# Ethernet.net
KiCad netlist of a schematic drawn in Altium Designer
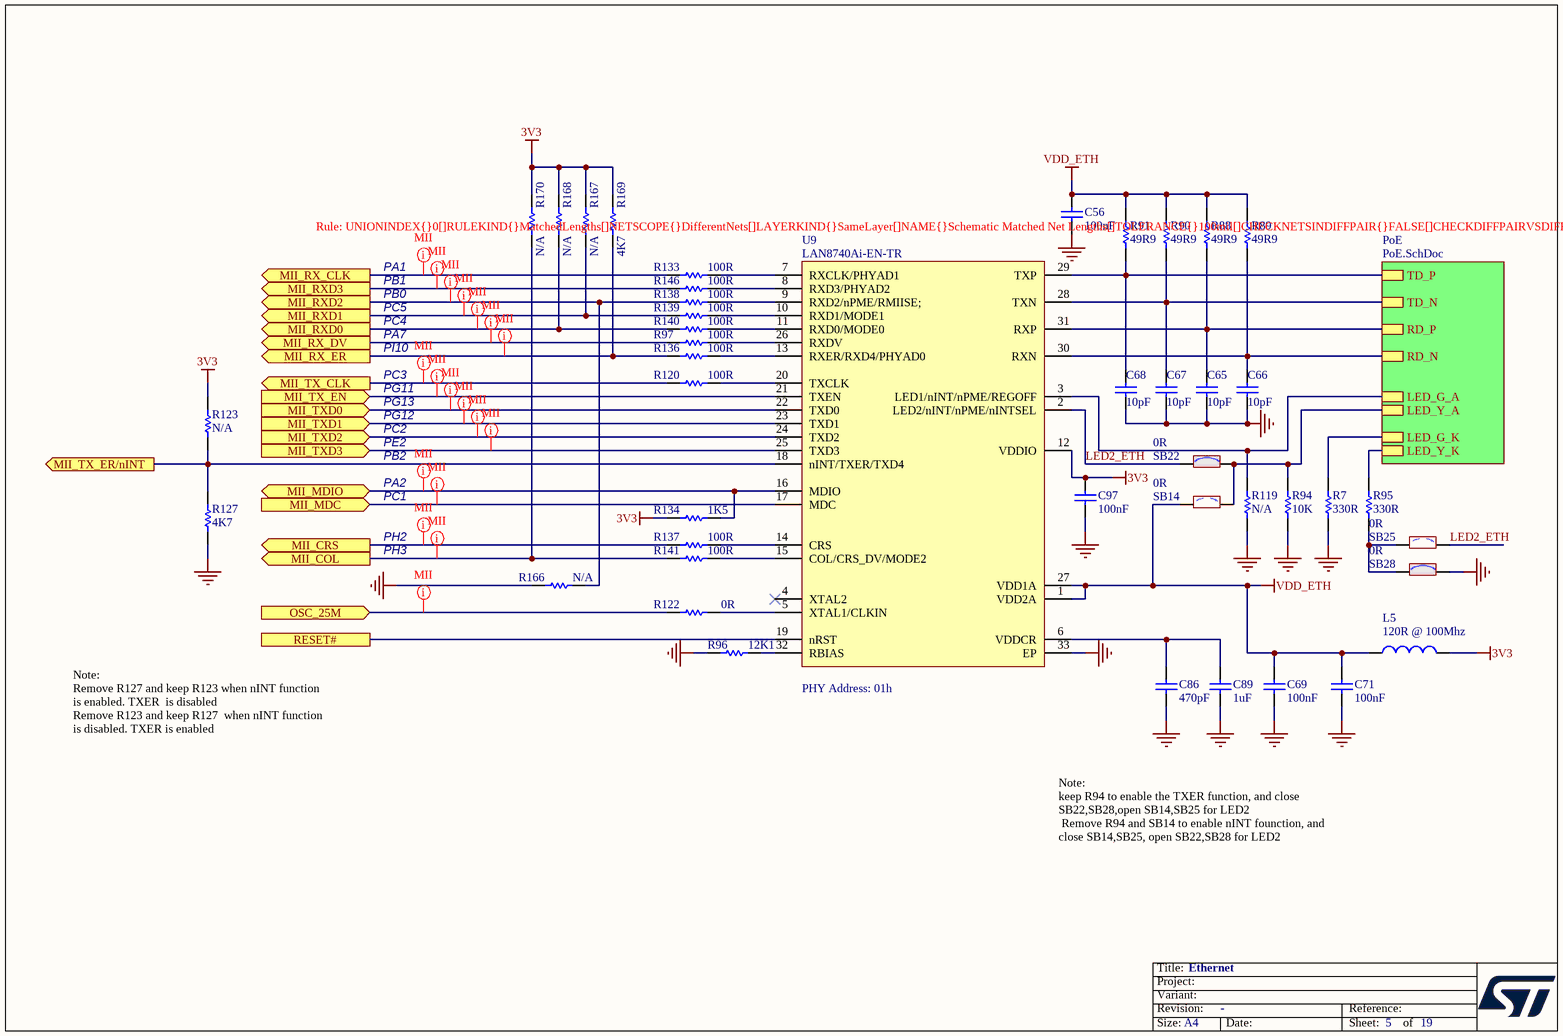
[diagram p0: Ethernet.SchDoc]

(export (version "E")
  (design (tool "Eeschema 10.0.6"))
  (components
    (comp (ref "C56")
      (value "100nF")
      (footprint "C0402")
      (description "Capacitor, MLCC, 100nF, 16V, X7R, +/-10%, 0402, T=0.5mm")
      (fields
        (field (name "INTERNAL_PART_NUMBER") "MCD-00006")
        (field (name "MANUFACTURER_PART_NUMBER") "CC0402KRX7R7BB104")
      )
      (libsource (lib "MCD_PARTS_database") (part "Capacitor"))
    )
    (comp (ref "C65")
      (value "10pF")
      (footprint "C0603")
      (description "Capacitor, MLCC, 10pF, 50V, NPO, 5%, 0603, T=0,8mm")
      (fields
        (field (name "INTERNAL_PART_NUMBER") "MCD-00637")
        (field (name "MANUFACTURER_PART_NUMBER") "CC0603JRNPO9BN100")
        (field (name "PROVIDED_BY") "subcon")
      )
      (libsource (lib "MCD_PARTS_database") (part "Capacitor"))
    )
    (comp (ref "C66")
      (value "10pF")
      (footprint "C0603")
      (description "Capacitor, MLCC, 10pF, 50V, NPO, 5%, 0603, T=0,8mm")
      (fields
        (field (name "INTERNAL_PART_NUMBER") "MCD-00637")
        (field (name "MANUFACTURER_PART_NUMBER") "CC0603JRNPO9BN100")
        (field (name "PROVIDED_BY") "subcon")
      )
      (libsource (lib "MCD_PARTS_database") (part "Capacitor"))
    )
    (comp (ref "C67")
      (value "10pF")
      (footprint "C0603")
      (description "Capacitor, MLCC, 10pF, 50V, NPO, 5%, 0603, T=0,8mm")
      (fields
        (field (name "INTERNAL_PART_NUMBER") "MCD-00637")
        (field (name "MANUFACTURER_PART_NUMBER") "CC0603JRNPO9BN100")
        (field (name "PROVIDED_BY") "subcon")
      )
      (libsource (lib "MCD_PARTS_database") (part "Capacitor"))
    )
    (comp (ref "C68")
      (value "10pF")
      (footprint "C0603")
      (description "Capacitor, MLCC, 10pF, 50V, NPO, 5%, 0603, T=0,8mm")
      (fields
        (field (name "INTERNAL_PART_NUMBER") "MCD-00637")
        (field (name "MANUFACTURER_PART_NUMBER") "CC0603JRNPO9BN100")
        (field (name "PROVIDED_BY") "subcon")
      )
      (libsource (lib "MCD_PARTS_database") (part "Capacitor"))
    )
    (comp (ref "C69")
      (value "100nF")
      (footprint "C0402")
      (description "Capacitor, MLCC, 100nF, 16V, X7R, +/-10%, 0402, T=0.5mm")
      (fields
        (field (name "INTERNAL_PART_NUMBER") "MCD-00006")
        (field (name "MANUFACTURER_PART_NUMBER") "CC0402KRX7R7BB104")
      )
      (libsource (lib "MCD_PARTS_database") (part "Capacitor"))
    )
    (comp (ref "C71")
      (value "100nF")
      (footprint "C0402")
      (description "Capacitor, MLCC, 100nF, 16V, X7R, +/-10%, 0402, T=0.5mm")
      (fields
        (field (name "INTERNAL_PART_NUMBER") "MCD-00006")
        (field (name "MANUFACTURER_PART_NUMBER") "CC0402KRX7R7BB104")
      )
      (libsource (lib "MCD_PARTS_database") (part "Capacitor"))
    )
    (comp (ref "C86")
      (value "470pF")
      (footprint "C0402")
      (description "Capacitor, MLCC, 470pF, 50V, NPO, 5%, 0402, T=0,5mm")
      (fields
        (field (name "INTERNAL_PART_NUMBER") "MCD-00724")
        (field (name "MANUFACTURER_PART_NUMBER") "CC0402JRNPO9BN471")
        (field (name "PROVIDED_BY") "Subcon")
      )
      (libsource (lib "MCD_PARTS_database") (part "Capacitor"))
    )
    (comp (ref "C89")
      (value "1uF")
      (footprint "C0603")
      (description "Capacitor, MLCC, 1uF, 16V, X5R, 10%, 0603, T=0,8mm")
      (fields
        (field (name "INTERNAL_PART_NUMBER") "MCD-00010")
        (field (name "MANUFACTURER_PART_NUMBER") "CC0603KRX5R7BB105")
        (field (name "PROVIDED_BY") "Subcon")
      )
      (libsource (lib "MCD_PARTS_database") (part "Capacitor"))
    )
    (comp (ref "C97")
      (value "100nF")
      (footprint "C0402")
      (description "Capacitor, MLCC, 100nF, 16V, X7R, +/-10%, 0402, T=0.5mm")
      (fields
        (field (name "INTERNAL_PART_NUMBER") "MCD-00006")
        (field (name "MANUFACTURER_PART_NUMBER") "CC0402KRX7R7BB104")
      )
      (libsource (lib "MCD_PARTS_database") (part "Capacitor"))
    )
    (comp (ref "L5")
      (value "120R @ 100Mhz")
      (footprint "FIL_0603_H0P65")
      (description "Bead,120R at 100Mhz,2A,0603")
      (fields
        (field (name "INTERNAL_PART_NUMBER") "MCD-00306")
        (field (name "MANUFACTURER_PART_NUMBER") "BLM18PG121SN1D")
        (field (name "PROVIDED_BY") "Subcon")
      )
      (libsource (lib "MCD_PARTS_database") (part "BEAD"))
    )
    (comp (ref "R7")
      (value "330R")
      (footprint "R0402")
      (description "Resistor,330R,0402,1%,1/16W")
      (fields
        (field (name "INTERNAL_PART_NUMBER") "MCD-00062")
        (field (name "MANUFACTURER_PART_NUMBER") "RC0402FR-07330RL")
        (field (name "PROVIDED_BY") "Subcon")
      )
      (libsource (lib "MCD_PARTS_database") (part "Resistor"))
    )
    (comp (ref "R88")
      (value "49R9")
      (footprint "R0402")
      (description "Resistor,49R9,0402,1%,1/16W")
      (fields
        (field (name "INTERNAL_PART_NUMBER") "MCD-00565")
        (field (name "MANUFACTURER_PART_NUMBER") "RC0402FR-0749R9L")
        (field (name "PROVIDED_BY") "Subcon")
      )
      (libsource (lib "MCD_PARTS_database") (part "Resistor"))
    )
    (comp (ref "R89")
      (value "49R9")
      (footprint "R0402")
      (description "Resistor,49R9,0402,1%,1/16W")
      (fields
        (field (name "INTERNAL_PART_NUMBER") "MCD-00565")
        (field (name "MANUFACTURER_PART_NUMBER") "RC0402FR-0749R9L")
        (field (name "PROVIDED_BY") "Subcon")
      )
      (libsource (lib "MCD_PARTS_database") (part "Resistor"))
    )
    (comp (ref "R90")
      (value "49R9")
      (footprint "R0402")
      (description "Resistor,49R9,0402,1%,1/16W")
      (fields
        (field (name "INTERNAL_PART_NUMBER") "MCD-00565")
        (field (name "MANUFACTURER_PART_NUMBER") "RC0402FR-0749R9L")
        (field (name "PROVIDED_BY") "Subcon")
      )
      (libsource (lib "MCD_PARTS_database") (part "Resistor"))
    )
    (comp (ref "R91")
      (value "49R9")
      (footprint "R0402")
      (description "Resistor,49R9,0402,1%,1/16W")
      (fields
        (field (name "INTERNAL_PART_NUMBER") "MCD-00565")
        (field (name "MANUFACTURER_PART_NUMBER") "RC0402FR-0749R9L")
        (field (name "PROVIDED_BY") "Subcon")
      )
      (libsource (lib "MCD_PARTS_database") (part "Resistor"))
    )
    (comp (ref "R94")
      (value "10K")
      (footprint "R0402")
      (description "Resistor,10K,0402,1%,1/16W")
      (fields
        (field (name "INTERNAL_PART_NUMBER") "MCD-00053")
        (field (name "MANUFACTURER_PART_NUMBER") "RC0402FR-0710KL")
        (field (name "PROVIDED_BY") "subcon")
      )
      (libsource (lib "MCD_PARTS_database") (part "Resistor"))
    )
    (comp (ref "R95")
      (value "330R")
      (footprint "R0402")
      (description "Resistor,330R,0402,1%,1/16W")
      (fields
        (field (name "INTERNAL_PART_NUMBER") "MCD-00062")
        (field (name "MANUFACTURER_PART_NUMBER") "RC0402FR-07330RL")
        (field (name "PROVIDED_BY") "Subcon")
      )
      (libsource (lib "MCD_PARTS_database") (part "Resistor"))
    )
    (comp (ref "R96")
      (value "12K1")
      (footprint "R0402")
      (description "Resistor,12K1,0402,1%,1/16W")
      (fields
        (field (name "INTERNAL_PART_NUMBER") "MCD-00723")
        (field (name "MANUFACTURER_PART_NUMBER") "RC0402FR-0712K1L")
        (field (name "PROVIDED_BY") "Subcon")
      )
      (libsource (lib "MCD_PARTS_database") (part "Resistor"))
    )
    (comp (ref "R97")
      (value "100R")
      (footprint "R0402")
      (description "Resistor, 100R, 0402, +/- 1%, 1/16W")
      (fields
        (field (name "INTERNAL_PART_NUMBER") "MCD-00067")
        (field (name "MANUFACTURER_PART_NUMBER") "RC0402FR-07100RL")
      )
      (libsource (lib "MCD_PARTS_database") (part "Resistor"))
    )
    (comp (ref "R119")
      (value "N/A")
      (footprint "R0402")
      (description "Resistor,10K,0402,1%,1/16W")
      (fields
        (field (name "INTERNAL_PART_NUMBER") "MCD-00053")
        (field (name "MANUFACTURER_PART_NUMBER") "RC0402FR-0710KL")
        (field (name "PROVIDED_BY") "subcon")
      )
      (libsource (lib "MCD_PARTS_database") (part "Resistor"))
    )
    (comp (ref "R120")
      (value "100R")
      (footprint "R0402")
      (description "Resistor, 100R, 0402, +/- 1%, 1/16W")
      (fields
        (field (name "INTERNAL_PART_NUMBER") "MCD-00067")
        (field (name "MANUFACTURER_PART_NUMBER") "RC0402FR-07100RL")
      )
      (libsource (lib "MCD_PARTS_database") (part "Resistor"))
    )
    (comp (ref "R122")
      (value "0R")
      (footprint "R0402")
      (description "Resistor,0R,0402,5%,1/16W")
      (fields
        (field (name "INTERNAL_PART_NUMBER") "MCD-00052")
        (field (name "MANUFACTURER_PART_NUMBER") "RC0402JR-070RL")
        (field (name "PROVIDED_BY") "Subcon")
      )
      (libsource (lib "MCD_PARTS_database") (part "Resistor"))
    )
    (comp (ref "R123")
      (value "N/A")
      (footprint "R0402")
      (description "Resistor,4K7,0402,1%,1/16W")
      (fields
        (field (name "INTERNAL_PART_NUMBER") "MCD-00065")
        (field (name "MANUFACTURER_PART_NUMBER") "RC0402FR-074K7L")
        (field (name "PROVIDED_BY") "Subcon")
      )
      (libsource (lib "MCD_PARTS_database") (part "Resistor"))
    )
    (comp (ref "R127")
      (value "4K7")
      (footprint "R0402")
      (description "Resistor,4K7,0402,1%,1/16W")
      (fields
        (field (name "INTERNAL_PART_NUMBER") "MCD-00065")
        (field (name "MANUFACTURER_PART_NUMBER") "RC0402FR-074K7L")
        (field (name "PROVIDED_BY") "Subcon")
      )
      (libsource (lib "MCD_PARTS_database") (part "Resistor"))
    )
    (comp (ref "R133")
      (value "100R")
      (footprint "R0402")
      (description "Resistor, 100R, 0402, +/- 1%, 1/16W")
      (fields
        (field (name "INTERNAL_PART_NUMBER") "MCD-00067")
        (field (name "MANUFACTURER_PART_NUMBER") "RC0402FR-07100RL")
      )
      (libsource (lib "MCD_PARTS_database") (part "Resistor"))
    )
    (comp (ref "R134")
      (value "1K5")
      (footprint "R0603")
      (description "Resistor,1K5,0603,1%,1/10W")
      (fields
        (field (name "INTERNAL_PART_NUMBER") "MCD-00217")
        (field (name "MANUFACTURER_PART_NUMBER") "RC0603FR-071K5L")
        (field (name "PROVIDED_BY") "Subcon")
      )
      (libsource (lib "MCD_PARTS_database") (part "Resistor"))
    )
    (comp (ref "R136")
      (value "100R")
      (footprint "R0402")
      (description "Resistor, 100R, 0402, +/- 1%, 1/16W")
      (fields
        (field (name "INTERNAL_PART_NUMBER") "MCD-00067")
        (field (name "MANUFACTURER_PART_NUMBER") "RC0402FR-07100RL")
      )
      (libsource (lib "MCD_PARTS_database") (part "Resistor"))
    )
    (comp (ref "R137")
      (value "100R")
      (footprint "R0402")
      (description "Resistor, 100R, 0402, +/- 1%, 1/16W")
      (fields
        (field (name "INTERNAL_PART_NUMBER") "MCD-00067")
        (field (name "MANUFACTURER_PART_NUMBER") "RC0402FR-07100RL")
      )
      (libsource (lib "MCD_PARTS_database") (part "Resistor"))
    )
    (comp (ref "R138")
      (value "100R")
      (footprint "R0402")
      (description "Resistor, 100R, 0402, +/- 1%, 1/16W")
      (fields
        (field (name "INTERNAL_PART_NUMBER") "MCD-00067")
        (field (name "MANUFACTURER_PART_NUMBER") "RC0402FR-07100RL")
      )
      (libsource (lib "MCD_PARTS_database") (part "Resistor"))
    )
    (comp (ref "R139")
      (value "100R")
      (footprint "R0402")
      (description "Resistor, 100R, 0402, +/- 1%, 1/16W")
      (fields
        (field (name "INTERNAL_PART_NUMBER") "MCD-00067")
        (field (name "MANUFACTURER_PART_NUMBER") "RC0402FR-07100RL")
      )
      (libsource (lib "MCD_PARTS_database") (part "Resistor"))
    )
    (comp (ref "R140")
      (value "100R")
      (footprint "R0402")
      (description "Resistor, 100R, 0402, +/- 1%, 1/16W")
      (fields
        (field (name "INTERNAL_PART_NUMBER") "MCD-00067")
        (field (name "MANUFACTURER_PART_NUMBER") "RC0402FR-07100RL")
      )
      (libsource (lib "MCD_PARTS_database") (part "Resistor"))
    )
    (comp (ref "R141")
      (value "100R")
      (footprint "R0402")
      (description "Resistor, 100R, 0402, +/- 1%, 1/16W")
      (fields
        (field (name "INTERNAL_PART_NUMBER") "MCD-00067")
        (field (name "MANUFACTURER_PART_NUMBER") "RC0402FR-07100RL")
      )
      (libsource (lib "MCD_PARTS_database") (part "Resistor"))
    )
    (comp (ref "R146")
      (value "100R")
      (footprint "R0402")
      (description "Resistor, 100R, 0402, +/- 1%, 1/16W")
      (fields
        (field (name "INTERNAL_PART_NUMBER") "MCD-00067")
        (field (name "MANUFACTURER_PART_NUMBER") "RC0402FR-07100RL")
      )
      (libsource (lib "MCD_PARTS_database") (part "Resistor"))
    )
    (comp (ref "R166")
      (value "N/A")
      (footprint "R0402")
      (description "Resistor,4K7,0402,1%,1/16W")
      (fields
        (field (name "INTERNAL_PART_NUMBER") "MCD-00065")
        (field (name "MANUFACTURER_PART_NUMBER") "RC0402FR-074K7L")
        (field (name "PROVIDED_BY") "Subcon")
      )
      (libsource (lib "MCD_PARTS_database") (part "Resistor"))
    )
    (comp (ref "R167")
      (value "N/A")
      (footprint "R0402")
      (description "Resistor,4K7,0402,1%,1/16W")
      (fields
        (field (name "INTERNAL_PART_NUMBER") "MCD-00065")
        (field (name "MANUFACTURER_PART_NUMBER") "RC0402FR-074K7L")
        (field (name "PROVIDED_BY") "Subcon")
      )
      (libsource (lib "MCD_PARTS_database") (part "Resistor"))
    )
    (comp (ref "R168")
      (value "N/A")
      (footprint "R0402")
      (description "Resistor,4K7,0402,1%,1/16W")
      (fields
        (field (name "INTERNAL_PART_NUMBER") "MCD-00065")
        (field (name "MANUFACTURER_PART_NUMBER") "RC0402FR-074K7L")
        (field (name "PROVIDED_BY") "Subcon")
      )
      (libsource (lib "MCD_PARTS_database") (part "Resistor"))
    )
    (comp (ref "R169")
      (value "4K7")
      (footprint "R0402")
      (description "Resistor,4K7,0402,1%,1/16W")
      (fields
        (field (name "INTERNAL_PART_NUMBER") "MCD-00065")
        (field (name "MANUFACTURER_PART_NUMBER") "RC0402FR-074K7L")
        (field (name "PROVIDED_BY") "Subcon")
      )
      (libsource (lib "MCD_PARTS_database") (part "Resistor"))
    )
    (comp (ref "R170")
      (value "N/A")
      (footprint "R0402")
      (description "Resistor,4K7,0402,1%,1/16W")
      (fields
        (field (name "INTERNAL_PART_NUMBER") "MCD-00065")
        (field (name "MANUFACTURER_PART_NUMBER") "RC0402FR-074K7L")
        (field (name "PROVIDED_BY") "Subcon")
      )
      (libsource (lib "MCD_PARTS_database") (part "Resistor"))
    )
    (comp (ref "SB14")
      (value "0R")
      (footprint "SOLDER-BRIDGE_R0603-0R")
      (description "Solder Bridge OFF")
      (fields (field (name "INTERNAL_PART_NUMBER") "MCD-00072") (field (name "MANUFACTURER") "YAGEO"))
      (libsource (lib "MCD_PARTS_database") (part "SB_OFF"))
    )
    (comp (ref "SB22")
      (value "0R")
      (footprint "SOLDER-BRIDGE_R0603-0R")
      (description "Solder Bridge ON")
      (fields
        (field (name "INTERNAL_PART_NUMBER") "MCD-00071")
        (field (name "MANUFACTURER") "YAGEO")
        (field (name "PROVIDED_BY") "Subcon")
      )
      (libsource (lib "MCD_PARTS_database") (part "SB_ON"))
    )
    (comp (ref "SB25")
      (value "0R")
      (footprint "SOLDER-BRIDGE_R0603-0R")
      (description "Solder Bridge OFF")
      (fields (field (name "INTERNAL_PART_NUMBER") "MCD-00072") (field (name "MANUFACTURER") "YAGEO"))
      (libsource (lib "MCD_PARTS_database") (part "SB_OFF"))
    )
    (comp (ref "SB28")
      (value "0R")
      (footprint "SOLDER-BRIDGE_R0603-0R")
      (description "Solder Bridge ON")
      (fields
        (field (name "INTERNAL_PART_NUMBER") "MCD-00071")
        (field (name "MANUFACTURER") "YAGEO")
        (field (name "PROVIDED_BY") "Subcon")
      )
      (libsource (lib "MCD_PARTS_database") (part "SB_ON"))
    )
    (comp (ref "U9")
      (value "LAN8740Ai-EN-TR")
      (footprint "ICC_QFN32-EPAD_5X5_P050")
      (fields
        (field (name "INTERNAL_PART_NUMBER") "MCD-01069")
        (field (name "MANUFACTURER") "MICROCHIP")
        (field (name "PROVIDED_BY") "Subcon")
      )
      (libsource (lib "MCD_PARTS_database") (part "LAN8740Ai-EN-TR"))
    )
  )
  (nets
    (net (code "1") (name "/LED2_ETH") (class "Default")
      (node (ref "SB22") (pin "1") (pinfunction "1_1") (pintype "passive"))
      (node (ref "SB25") (pin "2") (pinfunction "2_2") (pintype "passive"))
      (node (ref "U9") (pin "2") (pinfunction "LED2/nINT/nPME/nINTSEL_2") (pintype "passive"))
    )
    (net (code "2") (name "/LED_G_A") (class "Default")
      (node (ref "R119") (pin "1") (pinfunction "1_1") (pintype "passive"))
      (node (ref "U9") (pin "3") (pinfunction "LED1/nINT/nPME/REGOFF_3") (pintype "passive"))
    )
    (net (code "3") (name "/LED_G_K") (class "Default")
      (node (ref "R7") (pin "2") (pinfunction "2_2") (pintype "passive"))
    )
    (net (code "4") (name "/LED_Y_A") (class "Default")
      (node (ref "R94") (pin "2") (pinfunction "2_2") (pintype "passive"))
      (node (ref "SB14") (pin "2") (pinfunction "2_2") (pintype "passive"))
      (node (ref "SB22") (pin "2") (pinfunction "2_2") (pintype "passive"))
    )
    (net (code "5") (name "/LED_Y_K") (class "Default")
      (node (ref "R95") (pin "2") (pinfunction "2_2") (pintype "passive"))
    )
    (net (code "6") (name "/MII_COL") (class "Default")
      (node (ref "R141") (pin "1") (pinfunction "1_1") (pintype "passive"))
      (node (ref "R170") (pin "1") (pinfunction "1_1") (pintype "passive"))
    )
    (net (code "7") (name "/MII_CRS") (class "Default")
      (node (ref "R137") (pin "1") (pinfunction "1_1") (pintype "passive"))
    )
    (net (code "8") (name "/MII_MDC") (class "Default")
      (node (ref "U9") (pin "17") (pinfunction "MDC_17") (pintype "passive"))
    )
    (net (code "9") (name "/MII_MDIO") (class "Default")
      (node (ref "R134") (pin "1") (pinfunction "1_1") (pintype "passive"))
      (node (ref "U9") (pin "16") (pinfunction "MDIO_16") (pintype "passive"))
    )
    (net (code "10") (name "/MII_RXD0") (class "Default")
      (node (ref "R140") (pin "1") (pinfunction "1_1") (pintype "passive"))
      (node (ref "R168") (pin "1") (pinfunction "1_1") (pintype "passive"))
    )
    (net (code "11") (name "/MII_RXD1") (class "Default")
      (node (ref "R139") (pin "1") (pinfunction "1_1") (pintype "passive"))
      (node (ref "R167") (pin "1") (pinfunction "1_1") (pintype "passive"))
    )
    (net (code "12") (name "/MII_RXD2") (class "Default")
      (node (ref "R138") (pin "1") (pinfunction "1_1") (pintype "passive"))
      (node (ref "R166") (pin "1") (pinfunction "1_1") (pintype "passive"))
    )
    (net (code "13") (name "/MII_RXD3") (class "Default")
      (node (ref "R146") (pin "1") (pinfunction "1_1") (pintype "passive"))
    )
    (net (code "14") (name "/MII_RX_CLK") (class "Default")
      (node (ref "R133") (pin "1") (pinfunction "1_1") (pintype "passive"))
    )
    (net (code "15") (name "/MII_RX_DV") (class "Default")
      (node (ref "R97") (pin "1") (pinfunction "1_1") (pintype "passive"))
    )
    (net (code "16") (name "/MII_RX_ER") (class "Default")
      (node (ref "R136") (pin "1") (pinfunction "1_1") (pintype "passive"))
      (node (ref "R169") (pin "1") (pinfunction "1_1") (pintype "passive"))
    )
    (net (code "17") (name "/MII_TXD0") (class "Default")
      (node (ref "U9") (pin "22") (pinfunction "TXD0_22") (pintype "passive"))
    )
    (net (code "18") (name "/MII_TXD1") (class "Default")
      (node (ref "U9") (pin "23") (pinfunction "TXD1_23") (pintype "passive"))
    )
    (net (code "19") (name "/MII_TXD2") (class "Default")
      (node (ref "U9") (pin "24") (pinfunction "TXD2_24") (pintype "passive"))
    )
    (net (code "20") (name "/MII_TXD3") (class "Default")
      (node (ref "U9") (pin "25") (pinfunction "TXD3_25") (pintype "passive"))
    )
    (net (code "21") (name "/MII_TX_CLK") (class "Default")
      (node (ref "R120") (pin "1") (pinfunction "1_1") (pintype "passive"))
    )
    (net (code "22") (name "/MII_TX_EN") (class "Default")
      (node (ref "U9") (pin "21") (pinfunction "TXEN_21") (pintype "passive"))
    )
    (net (code "23") (name "/MII_TX_ER{slash}nINT") (class "Default")
      (node (ref "R123") (pin "2") (pinfunction "2_2") (pintype "passive"))
      (node (ref "R127") (pin "2") (pinfunction "2_2") (pintype "passive"))
      (node (ref "U9") (pin "18") (pinfunction "nINT/TXER/TXD4_18") (pintype "passive"))
    )
    (net (code "24") (name "/OSC_25M") (class "Default")
      (node (ref "R122") (pin "1") (pinfunction "1_1") (pintype "passive"))
    )
    (net (code "25") (name "/RD_N") (class "Default")
      (node (ref "C66") (pin "2") (pinfunction "2_2") (pintype "passive"))
      (node (ref "R89") (pin "1") (pinfunction "1_1") (pintype "passive"))
      (node (ref "U9") (pin "30") (pinfunction "RXN_30") (pintype "passive"))
    )
    (net (code "26") (name "/RD_P") (class "Default")
      (node (ref "C65") (pin "2") (pinfunction "2_2") (pintype "passive"))
      (node (ref "R88") (pin "1") (pinfunction "1_1") (pintype "passive"))
      (node (ref "U9") (pin "31") (pinfunction "RXP_31") (pintype "passive"))
    )
    (net (code "27") (name "/RESET#") (class "Default")
      (node (ref "U9") (pin "19") (pinfunction "nRST_19") (pintype "passive"))
    )
    (net (code "28") (name "/TD_N") (class "Default")
      (node (ref "C67") (pin "2") (pinfunction "2_2") (pintype "passive"))
      (node (ref "R90") (pin "1") (pinfunction "1_1") (pintype "passive"))
      (node (ref "U9") (pin "28") (pinfunction "TXN_28") (pintype "passive"))
    )
    (net (code "29") (name "/TD_P") (class "Default")
      (node (ref "C68") (pin "2") (pinfunction "2_2") (pintype "passive"))
      (node (ref "R91") (pin "1") (pinfunction "1_1") (pintype "passive"))
      (node (ref "U9") (pin "29") (pinfunction "TXP_29") (pintype "passive"))
    )
    (net (code "30") (name "3V3") (class "Default")
      (node (ref "C97") (pin "1") (pinfunction "1_1") (pintype "passive"))
      (node (ref "L5") (pin "2") (pinfunction "2_2") (pintype "passive"))
      (node (ref "R123") (pin "1") (pinfunction "1_1") (pintype "passive"))
      (node (ref "R134") (pin "2") (pinfunction "2_2") (pintype "passive"))
      (node (ref "R167") (pin "2") (pinfunction "2_2") (pintype "passive"))
      (node (ref "R168") (pin "2") (pinfunction "2_2") (pintype "passive"))
      (node (ref "R169") (pin "2") (pinfunction "2_2") (pintype "passive"))
      (node (ref "R170") (pin "2") (pinfunction "2_2") (pintype "passive"))
      (node (ref "U9") (pin "12") (pinfunction "VDDIO_12") (pintype "passive"))
    )
    (net (code "31") (name "GND") (class "Default")
      (node (ref "C56") (pin "1") (pinfunction "1_1") (pintype "passive"))
      (node (ref "C65") (pin "1") (pinfunction "1_1") (pintype "passive"))
      (node (ref "C66") (pin "1") (pinfunction "1_1") (pintype "passive"))
      (node (ref "C67") (pin "1") (pinfunction "1_1") (pintype "passive"))
      (node (ref "C68") (pin "1") (pinfunction "1_1") (pintype "passive"))
      (node (ref "C69") (pin "2") (pinfunction "2_2") (pintype "passive"))
      (node (ref "C71") (pin "2") (pinfunction "2_2") (pintype "passive"))
      (node (ref "C86") (pin "1") (pinfunction "1_1") (pintype "passive"))
      (node (ref "C89") (pin "1") (pinfunction "1_1") (pintype "passive"))
      (node (ref "C97") (pin "2") (pinfunction "2_2") (pintype "passive"))
      (node (ref "R119") (pin "2") (pinfunction "2_2") (pintype "passive"))
      (node (ref "R127") (pin "1") (pinfunction "1_1") (pintype "passive"))
      (node (ref "R166") (pin "2") (pinfunction "2_2") (pintype "passive"))
      (node (ref "R7") (pin "1") (pinfunction "1_1") (pintype "passive"))
      (node (ref "R94") (pin "1") (pinfunction "1_1") (pintype "passive"))
      (node (ref "R96") (pin "1") (pinfunction "1_1") (pintype "passive"))
      (node (ref "SB28") (pin "2") (pinfunction "2_2") (pintype "passive"))
      (node (ref "U9") (pin "33") (pinfunction "EP_33") (pintype "passive"))
    )
    (net (code "32") (name "Net-(R95-Pad1)") (class "Default")
      (node (ref "R95") (pin "1") (pinfunction "1_1") (pintype "passive"))
      (node (ref "SB25") (pin "1") (pinfunction "1_1") (pintype "passive"))
      (node (ref "SB28") (pin "1") (pinfunction "1_1") (pintype "passive"))
    )
    (net (code "33") (name "Net-(U9-COL{slash}CRS_DV{slash}MODE2)") (class "Default")
      (node (ref "R141") (pin "2") (pinfunction "2_2") (pintype "passive"))
      (node (ref "U9") (pin "15") (pinfunction "COL/CRS_DV/MODE2_15") (pintype "passive"))
    )
    (net (code "34") (name "Net-(U9-CRS)") (class "Default")
      (node (ref "R137") (pin "2") (pinfunction "2_2") (pintype "passive"))
      (node (ref "U9") (pin "14") (pinfunction "CRS_14") (pintype "passive"))
    )
    (net (code "35") (name "Net-(U9-RBIAS)") (class "Default")
      (node (ref "R96") (pin "2") (pinfunction "2_2") (pintype "passive"))
      (node (ref "U9") (pin "32") (pinfunction "RBIAS_32") (pintype "passive"))
    )
    (net (code "36") (name "Net-(U9-RXCLK{slash}PHYAD1)") (class "Default")
      (node (ref "R133") (pin "2") (pinfunction "2_2") (pintype "passive"))
      (node (ref "U9") (pin "7") (pinfunction "RXCLK/PHYAD1_7") (pintype "passive"))
    )
    (net (code "37") (name "Net-(U9-RXD0{slash}MODE0)") (class "Default")
      (node (ref "R140") (pin "2") (pinfunction "2_2") (pintype "passive"))
      (node (ref "U9") (pin "11") (pinfunction "RXD0/MODE0_11") (pintype "passive"))
    )
    (net (code "38") (name "Net-(U9-RXD1{slash}MODE1)") (class "Default")
      (node (ref "R139") (pin "2") (pinfunction "2_2") (pintype "passive"))
      (node (ref "U9") (pin "10") (pinfunction "RXD1/MODE1_10") (pintype "passive"))
    )
    (net (code "39") (name "Net-(U9-RXD2{slash}nPME{slash}RMIISE;)") (class "Default")
      (node (ref "R138") (pin "2") (pinfunction "2_2") (pintype "passive"))
      (node (ref "U9") (pin "9") (pinfunction "RXD2/nPME/RMIISE;_9") (pintype "passive"))
    )
    (net (code "40") (name "Net-(U9-RXD3{slash}PHYAD2)") (class "Default")
      (node (ref "R146") (pin "2") (pinfunction "2_2") (pintype "passive"))
      (node (ref "U9") (pin "8") (pinfunction "RXD3/PHYAD2_8") (pintype "passive"))
    )
    (net (code "41") (name "Net-(U9-RXDV)") (class "Default")
      (node (ref "R97") (pin "2") (pinfunction "2_2") (pintype "passive"))
      (node (ref "U9") (pin "26") (pinfunction "RXDV_26") (pintype "passive"))
    )
    (net (code "42") (name "Net-(U9-RXER{slash}RXD4{slash}PHYAD0)") (class "Default")
      (node (ref "R136") (pin "2") (pinfunction "2_2") (pintype "passive"))
      (node (ref "U9") (pin "13") (pinfunction "RXER/RXD4/PHYAD0_13") (pintype "passive"))
    )
    (net (code "43") (name "Net-(U9-TXCLK)") (class "Default")
      (node (ref "R120") (pin "2") (pinfunction "2_2") (pintype "passive"))
      (node (ref "U9") (pin "20") (pinfunction "TXCLK_20") (pintype "passive"))
    )
    (net (code "44") (name "Net-(U9-VDDCR)") (class "Default")
      (node (ref "C86") (pin "2") (pinfunction "2_2") (pintype "passive"))
      (node (ref "C89") (pin "2") (pinfunction "2_2") (pintype "passive"))
      (node (ref "U9") (pin "6") (pinfunction "VDDCR_6") (pintype "passive"))
    )
    (net (code "45") (name "Net-(U9-XTAL1{slash}CLKIN)") (class "Default")
      (node (ref "R122") (pin "2") (pinfunction "2_2") (pintype "passive"))
      (node (ref "U9") (pin "5") (pinfunction "XTAL1/CLKIN_5") (pintype "passive"))
    )
    (net (code "46") (name "VDD_ETH") (class "Default")
      (node (ref "C56") (pin "2") (pinfunction "2_2") (pintype "passive"))
      (node (ref "C69") (pin "1") (pinfunction "1_1") (pintype "passive"))
      (node (ref "C71") (pin "1") (pinfunction "1_1") (pintype "passive"))
      (node (ref "L5") (pin "1") (pinfunction "1_1") (pintype "passive"))
      (node (ref "R88") (pin "2") (pinfunction "2_2") (pintype "passive"))
      (node (ref "R89") (pin "2") (pinfunction "2_2") (pintype "passive"))
      (node (ref "R90") (pin "2") (pinfunction "2_2") (pintype "passive"))
      (node (ref "R91") (pin "2") (pinfunction "2_2") (pintype "passive"))
      (node (ref "SB14") (pin "1") (pinfunction "1_1") (pintype "passive"))
      (node (ref "U9") (pin "1") (pinfunction "VDD2A_1") (pintype "passive"))
      (node (ref "U9") (pin "27") (pinfunction "VDD1A_27") (pintype "passive"))
    )
    (net (code "47") (name "unconnected-(U9-XTAL2-Pad4)") (class "Default")
      (node (ref "U9") (pin "4") (pinfunction "XTAL2_4") (pintype "passive+no_connect"))
    )
  )
)
